# Digital_GPIO.net
KiCad netlist of a schematic drawn in Altium Designer
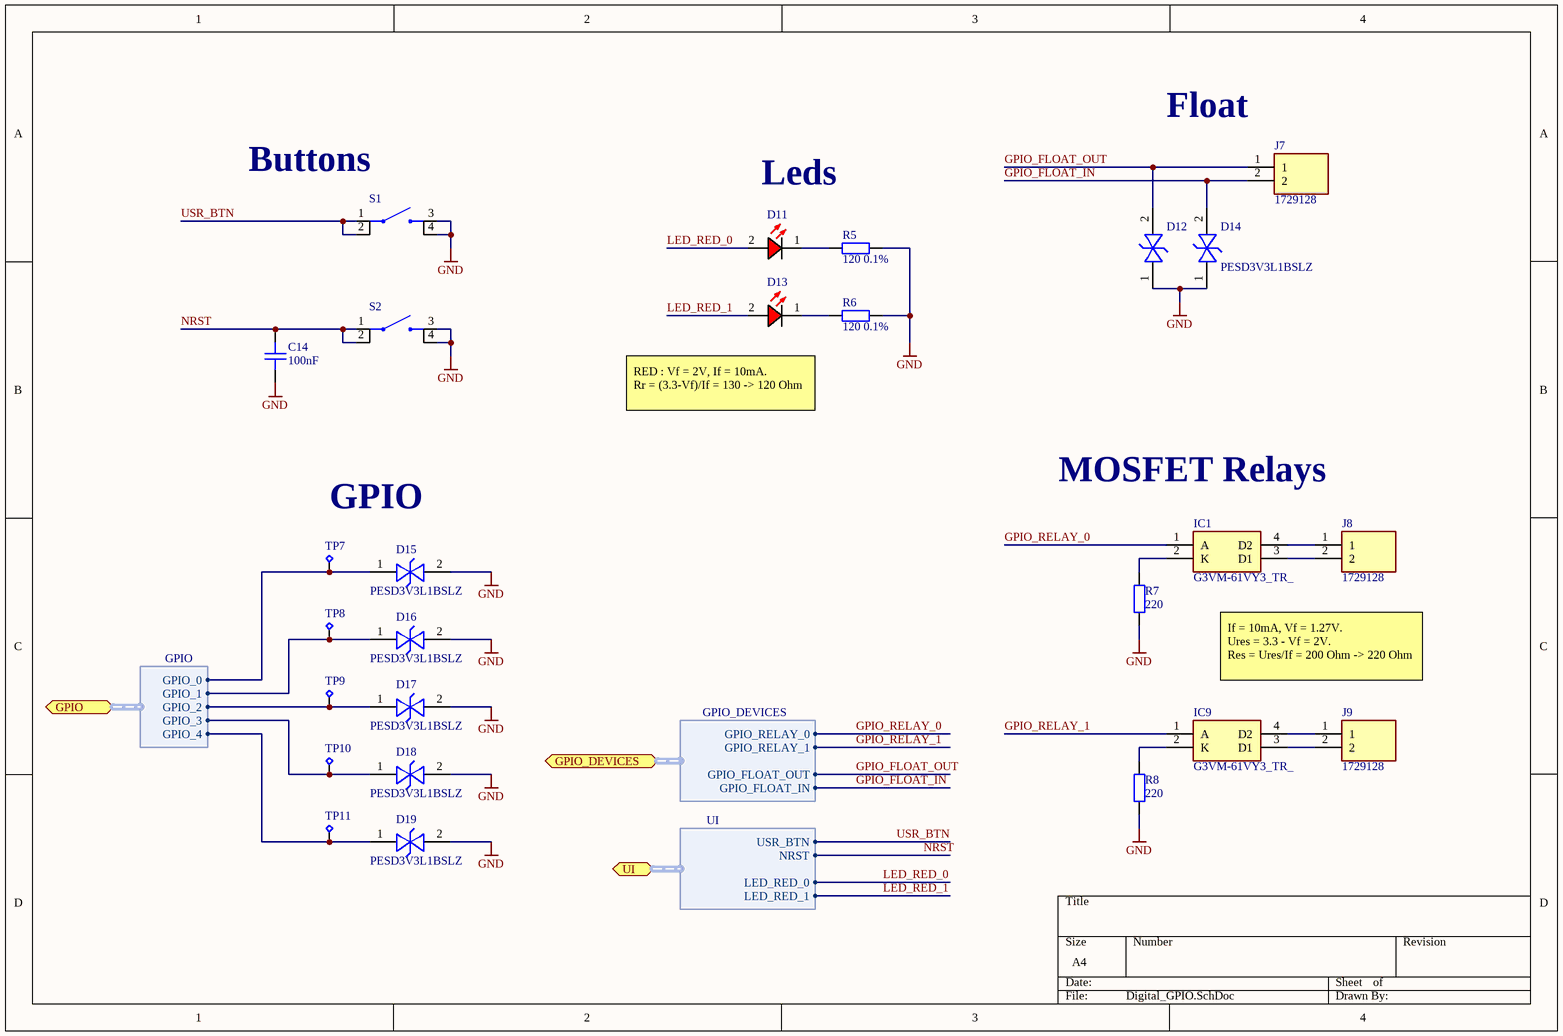
[diagram p0: Digital_GPIO.SchDoc]

(export (version "E")
  (design (tool "Eeschema 10.0.6"))
  (components
    (comp (ref "C14")
      (value "100nF")
      (footprint "CAPC1005X05N")
      (description "100nF 10% 50V Ceramic Capacitor X8L 0402 (1005 Metric)")
      (fields (field (name "TOLERANCE") "10%"))
      (libsource (lib "HEIG-VD Pro") (part "Capacitor"))
    )
    (comp (ref "D11")
      (value "LTST-C171KRKT")
      (footprint "LTST-C171")
      (description "Single Color LED, Red, Water Clear, 1.4mm")
      (libsource (lib "HEIG-VD Pro") (part "LED - Red"))
    )
    (comp (ref "D12")
      (value "PESD3V3L1BSLZ")
      (footprint "PESD3V3L1BSLZ")
      (description "Diode ESD (Bi-directional)")
      (fields (field (name "MOUSER PART NUMBER") "771-PESD3V3L1BSLZ"))
      (libsource (lib "Rainette") (part "PESD3V3L1BSLZ"))
    )
    (comp (ref "D13")
      (value "LTST-C171KRKT")
      (footprint "LTST-C171")
      (description "Single Color LED, Red, Water Clear, 1.4mm")
      (libsource (lib "HEIG-VD Pro") (part "LED - Red"))
    )
    (comp (ref "D14")
      (value "PESD3V3L1BSLZ")
      (footprint "PESD3V3L1BSLZ")
      (description "Diode ESD (Bi-directional)")
      (fields (field (name "MOUSER PART NUMBER") "771-PESD3V3L1BSLZ"))
      (libsource (lib "Rainette") (part "PESD3V3L1BSLZ"))
    )
    (comp (ref "D15")
      (value "PESD3V3L1BSLZ")
      (footprint "PESD3V3L1BSLZ")
      (description "Diode ESD (Bi-directional)")
      (fields (field (name "MOUSER PART NUMBER") "771-PESD3V3L1BSLZ"))
      (libsource (lib "Rainette") (part "PESD3V3L1BSLZ"))
    )
    (comp (ref "D16")
      (value "PESD3V3L1BSLZ")
      (footprint "PESD3V3L1BSLZ")
      (description "Diode ESD (Bi-directional)")
      (fields (field (name "MOUSER PART NUMBER") "771-PESD3V3L1BSLZ"))
      (libsource (lib "Rainette") (part "PESD3V3L1BSLZ"))
    )
    (comp (ref "D17")
      (value "PESD3V3L1BSLZ")
      (footprint "PESD3V3L1BSLZ")
      (description "Diode ESD (Bi-directional)")
      (fields (field (name "MOUSER PART NUMBER") "771-PESD3V3L1BSLZ"))
      (libsource (lib "Rainette") (part "PESD3V3L1BSLZ"))
    )
    (comp (ref "D18")
      (value "PESD3V3L1BSLZ")
      (footprint "PESD3V3L1BSLZ")
      (description "Diode ESD (Bi-directional)")
      (fields (field (name "MOUSER PART NUMBER") "771-PESD3V3L1BSLZ"))
      (libsource (lib "Rainette") (part "PESD3V3L1BSLZ"))
    )
    (comp (ref "D19")
      (value "PESD3V3L1BSLZ")
      (footprint "PESD3V3L1BSLZ")
      (description "Diode ESD (Bi-directional)")
      (fields (field (name "MOUSER PART NUMBER") "771-PESD3V3L1BSLZ"))
      (libsource (lib "Rainette") (part "PESD3V3L1BSLZ"))
    )
    (comp (ref "IC1")
      (value "G3VM-61VY3_TR_")
      (footprint "G3VM61VY3TR")
      (description "Integrated Circuit")
      (fields
        (field (name "MANUFACTURER_PART_NUMBER") "G3VM-61VY3(TR)")
        (field (name "MOUSER PART NUMBER") "653-G3VM-61VY3TR")
      )
      (libsource (lib "Rainette") (part "G3VM-61VY3_TR_"))
    )
    (comp (ref "IC9")
      (value "G3VM-61VY3_TR_")
      (footprint "G3VM61VY3TR")
      (description "Integrated Circuit")
      (fields
        (field (name "MANUFACTURER_PART_NUMBER") "G3VM-61VY3(TR)")
        (field (name "MOUSER PART NUMBER") "653-G3VM-61VY3TR")
      )
      (libsource (lib "Rainette") (part "G3VM-61VY3_TR_"))
    )
    (comp (ref "J7")
      (value "1729128")
      (footprint "1729128")
      (description "Connector")
      (fields (field (name "MOUSER PART NUMBER") "651-1729128"))
      (libsource (lib "Rainette") (part "1729128"))
    )
    (comp (ref "J8")
      (value "1729128")
      (footprint "1729128")
      (description "Connector")
      (fields (field (name "MOUSER PART NUMBER") "651-1729128"))
      (libsource (lib "Rainette") (part "1729128"))
    )
    (comp (ref "J9")
      (value "1729128")
      (footprint "1729128")
      (description "Connector")
      (fields (field (name "MOUSER PART NUMBER") "651-1729128"))
      (libsource (lib "Rainette") (part "1729128"))
    )
    (comp (ref "R5")
      (value "120 0.1%")
      (footprint "RESC2012X05N")
      (description "120 Ohms ±0.1% 0.125W, 1/8W Chip Resistor 0805 (2012 Metric) Thin Film\r\nRT0805BRD07120RL")
      (fields (field (name "POWER") "125mW") (field (name "TOLERANCE") "0.1%"))
      (libsource (lib "") (part "Resistor_1"))
    )
    (comp (ref "R6")
      (value "120 0.1%")
      (footprint "RESC2012X05N")
      (description "120 Ohms ±0.1% 0.125W, 1/8W Chip Resistor 0805 (2012 Metric) Thin Film")
      (fields (field (name "POWER") "125mW") (field (name "TOLERANCE") "0.1%"))
      (libsource (lib "") (part "Resistor_1"))
    )
    (comp (ref "R7")
      (value "220")
      (footprint "RESC1608X04N")
      (description "220 Ohms ±1% 0.1W, 1/10W Chip Resistor 0603 (1608 Metric) Moisture Resistant Thick Film")
      (fields (field (name "POWER") "100mW") (field (name "TOLERANCE") "1%"))
      (libsource (lib "HEIG-VD Pro") (part "Resistor"))
    )
    (comp (ref "R8")
      (value "220")
      (footprint "RESC1608X04N")
      (description "220 Ohms ±1% 0.1W, 1/10W Chip Resistor 0603 (1608 Metric) Moisture Resistant Thick Film")
      (fields (field (name "POWER") "100mW") (field (name "TOLERANCE") "1%"))
      (libsource (lib "HEIG-VD Pro") (part "Resistor"))
    )
    (comp (ref "S1")
      (value "PTS645SL43SMTR92LFS")
      (footprint "PTS645SL43SMTR92LFS")
      (libsource (lib "HEIG-VD Pro") (part "PTS526SK15SMTR2LFS"))
    )
    (comp (ref "S2")
      (value "PTS645SL43SMTR92LFS")
      (footprint "PTS645SL43SMTR92LFS")
      (libsource (lib "HEIG-VD Pro") (part "PTS526SK15SMTR2LFS"))
    )
    (comp (ref "TP7")
      (value "5117")
      (footprint "5117")
      (description "PC TEST POINT MINIATURE BLUE")
      (libsource (lib "HEIG-VD Pro") (part "Test Point PC THT"))
    )
    (comp (ref "TP8")
      (value "5117")
      (footprint "5117")
      (description "PC TEST POINT MINIATURE BLUE")
      (libsource (lib "HEIG-VD Pro") (part "Test Point PC THT"))
    )
    (comp (ref "TP9")
      (value "5117")
      (footprint "5117")
      (description "PC TEST POINT MINIATURE BLUE")
      (libsource (lib "HEIG-VD Pro") (part "Test Point PC THT"))
    )
    (comp (ref "TP10")
      (value "5117")
      (footprint "5117")
      (description "PC TEST POINT MINIATURE BLUE")
      (libsource (lib "HEIG-VD Pro") (part "Test Point PC THT"))
    )
    (comp (ref "TP11")
      (value "5117")
      (footprint "5117")
      (description "PC TEST POINT MINIATURE BLUE")
      (libsource (lib "HEIG-VD Pro") (part "Test Point PC THT"))
    )
  )
  (nets
    (net (code "4") (name "/GPIO_FLOAT_IN") (class "Default")
      (node (ref "D14") (pin "2") (pinfunction "K2_2") (pintype "passive"))
      (node (ref "J7") (pin "2") (pinfunction "2_2") (pintype "passive"))
    )
    (net (code "5") (name "/GPIO_FLOAT_OUT") (class "Default")
      (node (ref "D12") (pin "2") (pinfunction "K2_2") (pintype "passive"))
      (node (ref "J7") (pin "1") (pinfunction "1_1") (pintype "passive"))
    )
    (net (code "6") (name "/GPIO_RELAY_0") (class "Default")
      (node (ref "IC1") (pin "1") (pinfunction "A_1") (pintype "passive"))
    )
    (net (code "7") (name "/GPIO_RELAY_1") (class "Default")
      (node (ref "IC9") (pin "1") (pinfunction "A_1") (pintype "passive"))
    )
    (net (code "8") (name "/LED_RED_0") (class "Default")
      (node (ref "D11") (pin "2") (pinfunction "A_2") (pintype "passive"))
    )
    (net (code "9") (name "/LED_RED_1") (class "Default")
      (node (ref "D13") (pin "2") (pinfunction "A_2") (pintype "passive"))
    )
    (net (code "10") (name "/NRST") (class "Default")
      (node (ref "C14") (pin "1") (pinfunction "1_1") (pintype "passive"))
      (node (ref "S2") (pin "1") (pinfunction "1_1") (pintype "passive"))
      (node (ref "S2") (pin "2") (pinfunction "2_2") (pintype "passive"))
    )
    (net (code "11") (name "/USR_BTN") (class "Default")
      (node (ref "S1") (pin "1") (pinfunction "1_1") (pintype "passive"))
      (node (ref "S1") (pin "2") (pinfunction "2_2") (pintype "passive"))
    )
    (net (code "15") (name "GND") (class "Default")
      (node (ref "C14") (pin "2") (pinfunction "2_2") (pintype "passive"))
      (node (ref "D12") (pin "1") (pinfunction "K1_1") (pintype "passive"))
      (node (ref "D14") (pin "1") (pinfunction "K1_1") (pintype "passive"))
      (node (ref "D15") (pin "2") (pinfunction "K2_2") (pintype "passive"))
      (node (ref "D16") (pin "2") (pinfunction "K2_2") (pintype "passive"))
      (node (ref "D17") (pin "2") (pinfunction "K2_2") (pintype "passive"))
      (node (ref "D18") (pin "2") (pinfunction "K2_2") (pintype "passive"))
      (node (ref "D19") (pin "2") (pinfunction "K2_2") (pintype "passive"))
      (node (ref "R5") (pin "2") (pinfunction "2_2") (pintype "passive"))
      (node (ref "R6") (pin "2") (pinfunction "2_2") (pintype "passive"))
      (node (ref "R7") (pin "1") (pinfunction "1_1") (pintype "passive"))
      (node (ref "R8") (pin "1") (pinfunction "1_1") (pintype "passive"))
      (node (ref "S1") (pin "3") (pinfunction "3_3") (pintype "passive"))
      (node (ref "S1") (pin "4") (pinfunction "4_4") (pintype "passive"))
      (node (ref "S2") (pin "3") (pinfunction "3_3") (pintype "passive"))
      (node (ref "S2") (pin "4") (pinfunction "4_4") (pintype "passive"))
    )
    (net (code "16") (name "Net-(D11-K)") (class "Default")
      (node (ref "D11") (pin "1") (pinfunction "K_1") (pintype "passive"))
      (node (ref "R5") (pin "1") (pinfunction "1_1") (pintype "passive"))
    )
    (net (code "17") (name "Net-(D13-K)") (class "Default")
      (node (ref "D13") (pin "1") (pinfunction "K_1") (pintype "passive"))
      (node (ref "R6") (pin "1") (pinfunction "1_1") (pintype "passive"))
    )
    (net (code "18") (name "Net-(D15-K1)") (class "Default")
      (node (ref "D15") (pin "1") (pinfunction "K1_1") (pintype "passive"))
      (node (ref "TP7") (pin "1") (pinfunction "1_1") (pintype "passive"))
    )
    (net (code "19") (name "Net-(D16-K1)") (class "Default")
      (node (ref "D16") (pin "1") (pinfunction "K1_1") (pintype "passive"))
      (node (ref "TP8") (pin "1") (pinfunction "1_1") (pintype "passive"))
    )
    (net (code "20") (name "Net-(D17-K1)") (class "Default")
      (node (ref "D17") (pin "1") (pinfunction "K1_1") (pintype "passive"))
      (node (ref "TP9") (pin "1") (pinfunction "1_1") (pintype "passive"))
    )
    (net (code "21") (name "Net-(D18-K1)") (class "Default")
      (node (ref "D18") (pin "1") (pinfunction "K1_1") (pintype "passive"))
      (node (ref "TP10") (pin "1") (pinfunction "1_1") (pintype "passive"))
    )
    (net (code "22") (name "Net-(D19-K1)") (class "Default")
      (node (ref "D19") (pin "1") (pinfunction "K1_1") (pintype "passive"))
      (node (ref "TP11") (pin "1") (pinfunction "1_1") (pintype "passive"))
    )
    (net (code "23") (name "Net-(IC1-D1)") (class "Default")
      (node (ref "IC1") (pin "3") (pinfunction "D1_3") (pintype "passive"))
      (node (ref "J8") (pin "2") (pinfunction "2_2") (pintype "passive"))
    )
    (net (code "24") (name "Net-(IC1-D2)") (class "Default")
      (node (ref "IC1") (pin "4") (pinfunction "D2_4") (pintype "passive"))
      (node (ref "J8") (pin "1") (pinfunction "1_1") (pintype "passive"))
    )
    (net (code "25") (name "Net-(IC1-K)") (class "Default")
      (node (ref "IC1") (pin "2") (pinfunction "K_2") (pintype "passive"))
      (node (ref "R7") (pin "2") (pinfunction "2_2") (pintype "passive"))
    )
    (net (code "26") (name "Net-(IC9-D1)") (class "Default")
      (node (ref "IC9") (pin "3") (pinfunction "D1_3") (pintype "passive"))
      (node (ref "J9") (pin "2") (pinfunction "2_2") (pintype "passive"))
    )
    (net (code "27") (name "Net-(IC9-D2)") (class "Default")
      (node (ref "IC9") (pin "4") (pinfunction "D2_4") (pintype "passive"))
      (node (ref "J9") (pin "1") (pinfunction "1_1") (pintype "passive"))
    )
    (net (code "28") (name "Net-(IC9-K)") (class "Default")
      (node (ref "IC9") (pin "2") (pinfunction "K_2") (pintype "passive"))
      (node (ref "R8") (pin "2") (pinfunction "2_2") (pintype "passive"))
    )
  )
)
